# Sheet1.net
KiCad netlist of a schematic drawn in Altium Designer
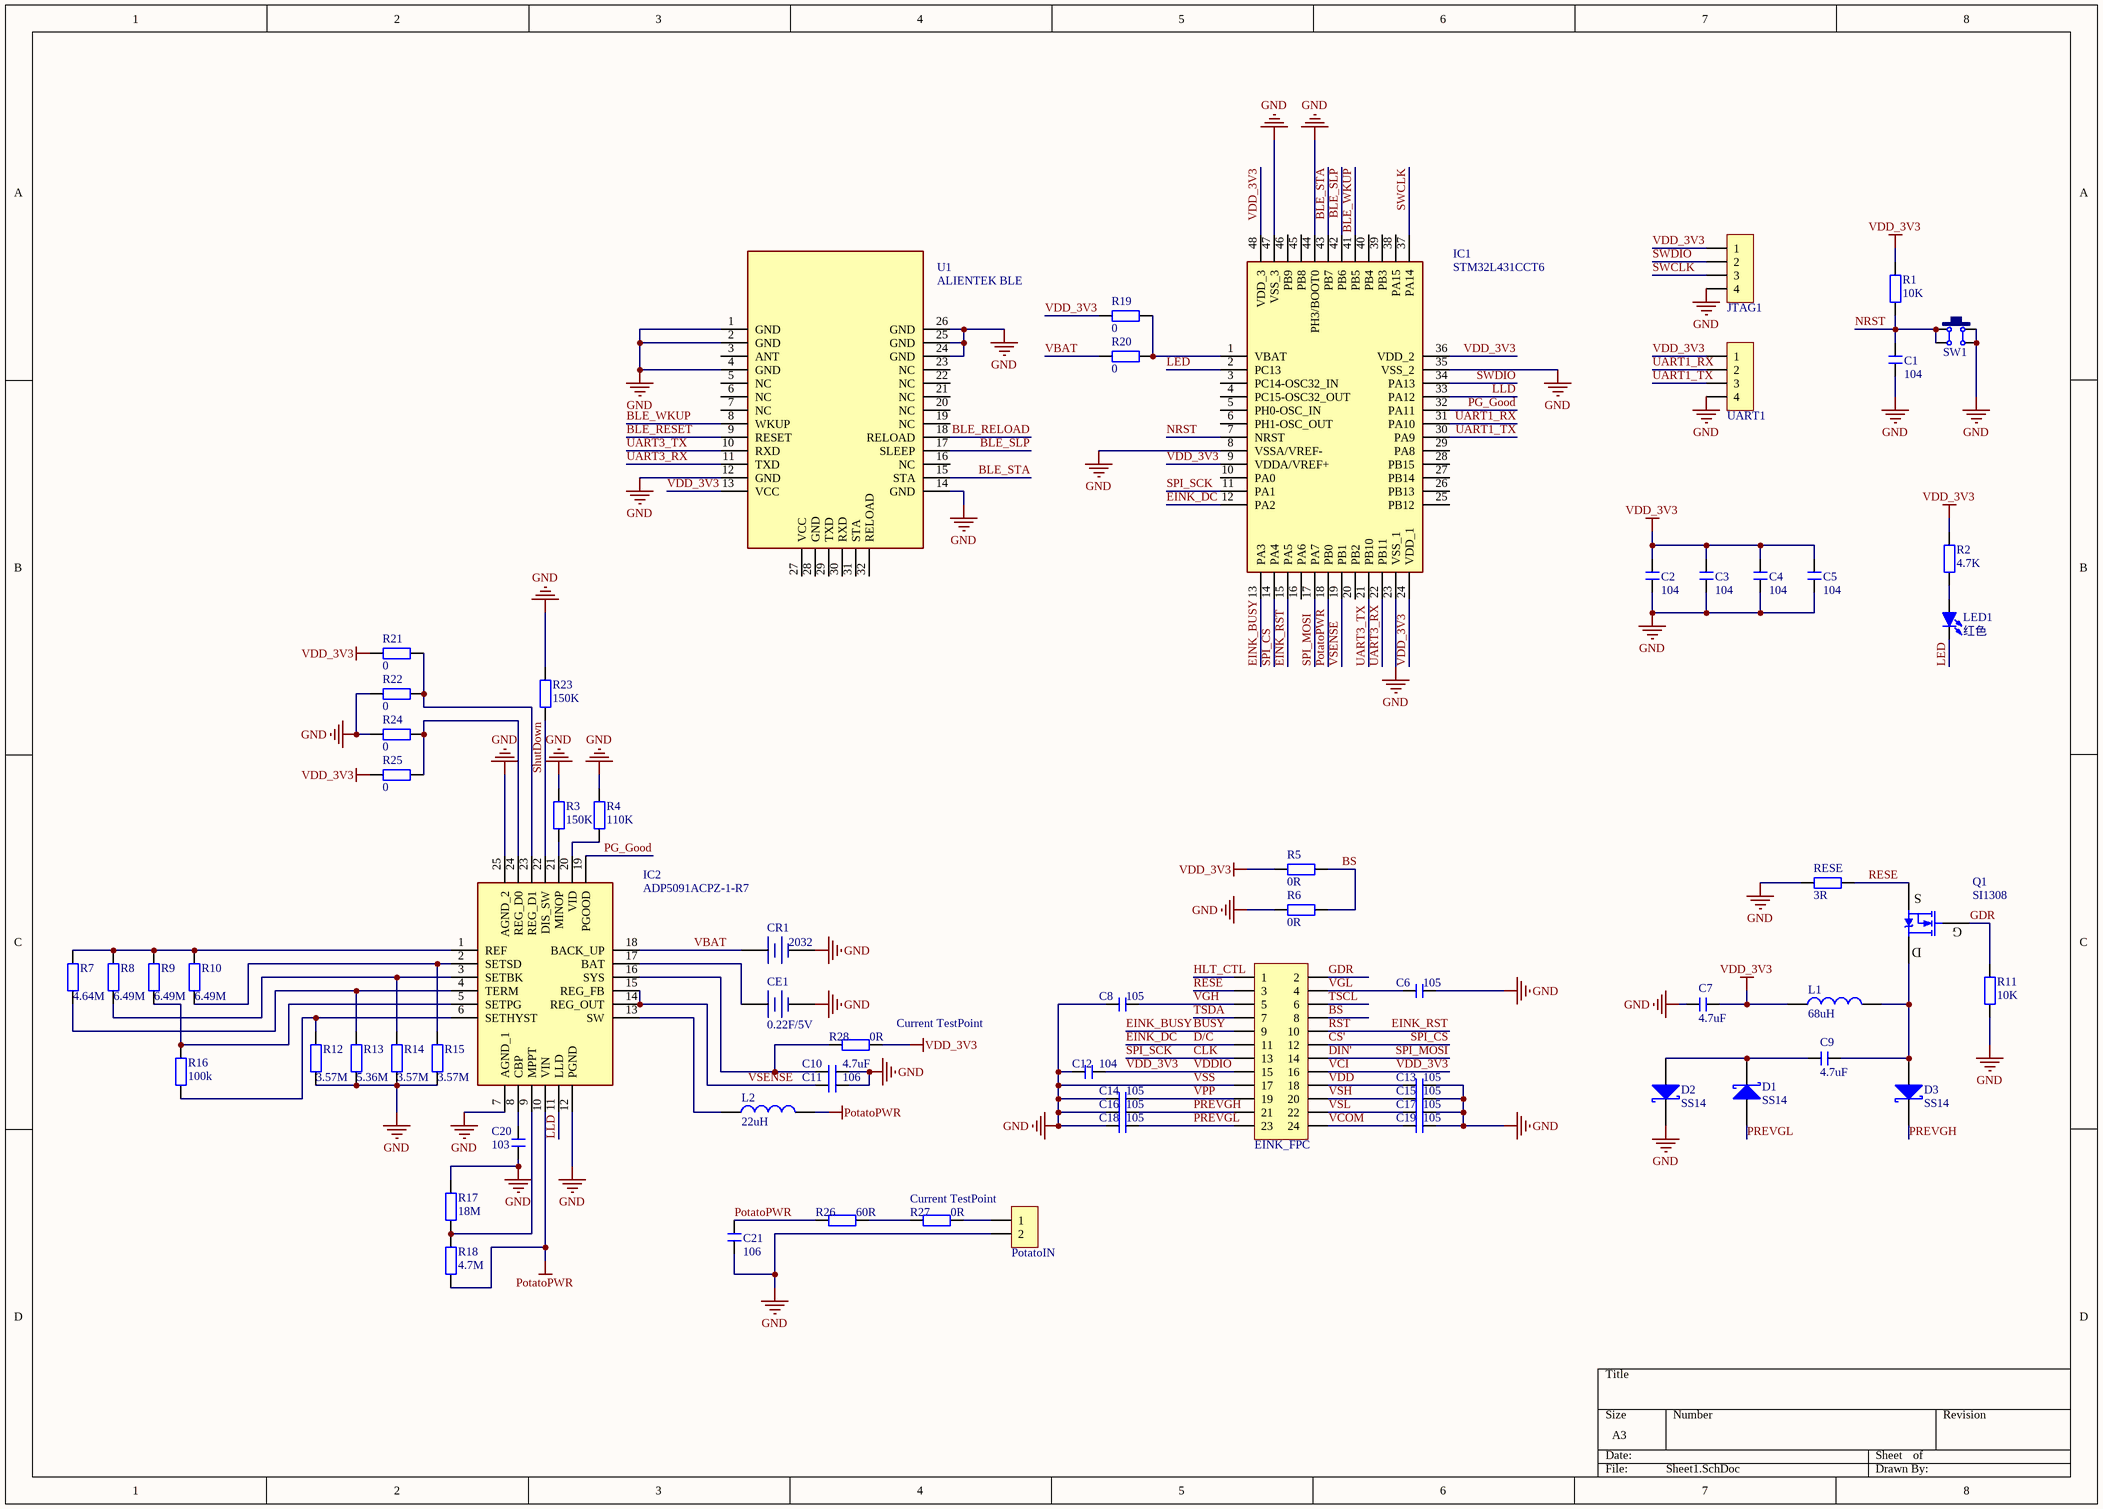
[diagram p0: Sheet1.SchDoc]

(export (version "E")
  (design (tool "Eeschema 10.0.6"))
  (components
    (comp (ref "C1")
      (value "104")
      (footprint "C 0603_L")
      (description "贴片电容")
      (libsource (lib "0.1 - 电阻-电容-电感") (part "C"))
    )
    (comp (ref "C2")
      (value "104")
      (footprint "C 0603_L")
      (description "贴片电容")
      (libsource (lib "0.1 - 电阻-电容-电感") (part "C"))
    )
    (comp (ref "C3")
      (value "104")
      (footprint "C 0603_L")
      (description "贴片电容")
      (libsource (lib "0.1 - 电阻-电容-电感") (part "C"))
    )
    (comp (ref "C4")
      (value "104")
      (footprint "C 0603_L")
      (description "贴片电容")
      (libsource (lib "0.1 - 电阻-电容-电感") (part "C"))
    )
    (comp (ref "C5")
      (value "104")
      (footprint "C 0603_L")
      (description "贴片电容")
      (libsource (lib "0.1 - 电阻-电容-电感") (part "C"))
    )
    (comp (ref "C6")
      (value "105")
      (footprint "C 0603_L")
      (description "贴片电容")
      (libsource (lib "0.1 - 电阻-电容-电感") (part "C"))
    )
    (comp (ref "C7")
      (value "4.7uF")
      (footprint "C 0603_L")
      (description "贴片电容")
      (libsource (lib "0.1 - 电阻-电容-电感") (part "C"))
    )
    (comp (ref "C8")
      (value "105")
      (footprint "C 0603_L")
      (description "贴片电容")
      (libsource (lib "0.1 - 电阻-电容-电感") (part "C"))
    )
    (comp (ref "C9")
      (value "4.7uF")
      (footprint "C 0603_L")
      (description "贴片电容")
      (libsource (lib "0.1 - 电阻-电容-电感") (part "C"))
    )
    (comp (ref "C10")
      (value "4.7uF")
      (footprint "C 0603_L")
      (description "贴片电容")
      (libsource (lib "0.1 - 电阻-电容-电感") (part "C"))
    )
    (comp (ref "C11")
      (value "106")
      (footprint "C 0603_L")
      (description "贴片电容")
      (libsource (lib "0.1 - 电阻-电容-电感") (part "C"))
    )
    (comp (ref "C12")
      (value "104")
      (footprint "C 0603_L")
      (description "贴片电容")
      (libsource (lib "0.1 - 电阻-电容-电感") (part "C"))
    )
    (comp (ref "C13")
      (value "105")
      (footprint "C 0603_L")
      (description "贴片电容")
      (libsource (lib "0.1 - 电阻-电容-电感") (part "C"))
    )
    (comp (ref "C14")
      (value "105")
      (footprint "C 0603_L")
      (description "贴片电容")
      (libsource (lib "0.1 - 电阻-电容-电感") (part "C"))
    )
    (comp (ref "C15")
      (value "105")
      (footprint "C 0603_L")
      (description "贴片电容")
      (libsource (lib "0.1 - 电阻-电容-电感") (part "C"))
    )
    (comp (ref "C16")
      (value "105")
      (footprint "C 0603_L")
      (description "贴片电容")
      (libsource (lib "0.1 - 电阻-电容-电感") (part "C"))
    )
    (comp (ref "C17")
      (value "105")
      (footprint "C 0603_L")
      (description "贴片电容")
      (libsource (lib "0.1 - 电阻-电容-电感") (part "C"))
    )
    (comp (ref "C18")
      (value "105")
      (footprint "C 0603_L")
      (description "贴片电容")
      (libsource (lib "0.1 - 电阻-电容-电感") (part "C"))
    )
    (comp (ref "C19")
      (value "105")
      (footprint "C 0603_L")
      (description "贴片电容")
      (libsource (lib "0.1 - 电阻-电容-电感") (part "C"))
    )
    (comp (ref "C20")
      (value "103")
      (footprint "C 0603_L")
      (description "贴片电容")
      (libsource (lib "0.1 - 电阻-电容-电感") (part "C"))
    )
    (comp (ref "C21")
      (value "106")
      (footprint "C 0603_L")
      (description "贴片电容")
      (libsource (lib "0.1 - 电阻-电容-电感") (part "C"))
    )
    (comp (ref "CE1")
      (value "0.22F/5V")
      (footprint "CAP 5.0*12.5*20 - BK")
      (description "微型电池")
      (fields (field (name "版权归属") "封装库来自淘宝 ID：黄晶宝石"))
      (libsource (lib "4.1 - 未分类器件") (part "CR-3V"))
    )
    (comp (ref "CR1")
      (value "2032")
      (footprint "CR2032_A")
      (description "微型电池")
      (fields (field (name "版权归属") "封装库来自淘宝 ID：黄晶宝石"))
      (libsource (lib "4.1 - 未分类器件") (part "CR-3V"))
    )
    (comp (ref "D1")
      (value "SS14")
      (footprint "SOD-123")
      (description "肖特基二极管")
      (libsource (lib "0.2 -  二极管-整流桥") (part "SS14"))
    )
    (comp (ref "D2")
      (value "SS14")
      (footprint "SOD-123")
      (description "肖特基二极管")
      (libsource (lib "0.2 -  二极管-整流桥") (part "SS14"))
    )
    (comp (ref "D3")
      (value "SS14")
      (footprint "SOD-123")
      (description "肖特基二极管")
      (libsource (lib "0.2 -  二极管-整流桥") (part "SS14"))
    )
    (comp (ref "EINK_FPC")
      (value "Header 2X11")
      (footprint "FPC0.5 2H-WS-24P")
      (description "12*2P接插件")
      (fields (field (name "版权归属") "封装库来自淘宝卖家 ID：黄晶宝石"))
      (libsource (lib "5.3 - 接插件-脚距2.54 (100mil) ") (part "Header 12X2"))
    )
    (comp (ref "IC1")
      (value "STM32L431CCT6")
      (footprint "SkylakeADPcbLib:QFP50P900X900X160-48N")
      (description "Integrated Circuit")
      (libsource (lib "*") (part "STM32L431CCT6"))
    )
    (comp (ref "IC2")
      (value "ADP5091ACPZ-1-R7")
      (footprint "SkylakeADPcbLib:QFN50P400X400X80-25N-D")
      (description "Integrated Circuit")
      (libsource (lib "*") (part "ADP5091ACPZ-1-R7"))
    )
    (comp (ref "JTAG1")
      (value "HDR-1X4")
      (footprint "XH2.54-LI-4P")
      (description "4P接插件")
      (libsource (lib "5.0 - 接插件-脚距1.25") (part "Header 4"))
    )
    (comp (ref "L1")
      (value "68uH")
      (footprint "CDRH74")
      (description "小功率贴片电感")
      (libsource (lib "0.1 - 电阻-电容-电感") (part "L"))
    )
    (comp (ref "L2")
      (value "22uH")
      (footprint "CDRH74")
      (description "小功率贴片电感")
      (libsource (lib "0.1 - 电阻-电容-电感") (part "L"))
    )
    (comp (ref "LED1")
      (value "红色")
      (footprint "LED 0603R")
      (description "贴片LED")
      (fields (field (name "版权归属") "封装库来自淘宝 ID：黄晶宝石"))
      (libsource (lib "0.3 - LED发光二极管") (part "LED-SMD"))
    )
    (comp (ref "PotatoIN")
      (value "HDR-1X2")
      (footprint "XH2.54-LI-2P")
      (description "2P接插件")
      (fields (field (name "版权归属") "封装库来自淘宝 ID：黄晶宝石"))
      (libsource (lib "5.3 - 接插件-脚距2.54 (100mil) ") (part "Header 2"))
    )
    (comp (ref "Q1")
      (value "SI1308")
      (footprint "SOT23-3N")
      (description "N沟道场效应管")
      (libsource (lib "0.5 - 场效应管-可控硅") (part "SI2302"))
    )
    (comp (ref "R1")
      (value "10K")
      (footprint "R 0603_L")
      (description "贴片电阻")
      (fields (field (name "版权归属") "来自淘宝 ID：黄晶宝石"))
      (libsource (lib "0.1 - 电阻-电容-电感") (part "R"))
    )
    (comp (ref "R2")
      (value "4.7K")
      (footprint "R 0603_L")
      (description "贴片电阻")
      (fields (field (name "版权归属") "来自淘宝 ID：黄晶宝石"))
      (libsource (lib "0.1 - 电阻-电容-电感") (part "R"))
    )
    (comp (ref "R3")
      (value "150K")
      (footprint "R 0603_L")
      (description "贴片电阻")
      (fields (field (name "版权归属") "来自淘宝 ID：黄晶宝石"))
      (libsource (lib "0.1 - 电阻-电容-电感") (part "R"))
    )
    (comp (ref "R4")
      (value "110K")
      (footprint "R 0603_L")
      (description "贴片电阻")
      (fields (field (name "版权归属") "来自淘宝 ID：黄晶宝石"))
      (libsource (lib "0.1 - 电阻-电容-电感") (part "R"))
    )
    (comp (ref "R5")
      (value "0R")
      (footprint "R 0603_L")
      (description "贴片电阻")
      (fields (field (name "版权归属") "来自淘宝 ID：黄晶宝石"))
      (libsource (lib "0.1 - 电阻-电容-电感") (part "R"))
    )
    (comp (ref "R6")
      (value "0R")
      (footprint "R 0603_L")
      (description "贴片电阻")
      (fields (field (name "版权归属") "来自淘宝 ID：黄晶宝石"))
      (libsource (lib "0.1 - 电阻-电容-电感") (part "R"))
    )
    (comp (ref "R7")
      (value "4.64M")
      (footprint "R 0603_L")
      (description "贴片电阻")
      (fields (field (name "版权归属") "来自淘宝 ID：黄晶宝石"))
      (libsource (lib "0.1 - 电阻-电容-电感") (part "R"))
    )
    (comp (ref "R8")
      (value "6.49M")
      (footprint "R 0603_L")
      (description "贴片电阻")
      (fields (field (name "版权归属") "来自淘宝 ID：黄晶宝石"))
      (libsource (lib "0.1 - 电阻-电容-电感") (part "R"))
    )
    (comp (ref "R9")
      (value "6.49M")
      (footprint "R 0603_L")
      (description "贴片电阻")
      (fields (field (name "版权归属") "来自淘宝 ID：黄晶宝石"))
      (libsource (lib "0.1 - 电阻-电容-电感") (part "R"))
    )
    (comp (ref "R10")
      (value "6.49M")
      (footprint "R 0603_L")
      (description "贴片电阻")
      (fields (field (name "版权归属") "来自淘宝 ID：黄晶宝石"))
      (libsource (lib "0.1 - 电阻-电容-电感") (part "R"))
    )
    (comp (ref "R11")
      (value "10K")
      (footprint "R 0603_L")
      (description "贴片电阻")
      (fields (field (name "版权归属") "来自淘宝 ID：黄晶宝石"))
      (libsource (lib "0.1 - 电阻-电容-电感") (part "R"))
    )
    (comp (ref "R12")
      (value "3.57M")
      (footprint "R 0603_L")
      (description "贴片电阻")
      (fields (field (name "版权归属") "来自淘宝 ID：黄晶宝石"))
      (libsource (lib "0.1 - 电阻-电容-电感") (part "R"))
    )
    (comp (ref "R13")
      (value "5.36M")
      (footprint "R 0603_L")
      (description "贴片电阻")
      (fields (field (name "版权归属") "来自淘宝 ID：黄晶宝石"))
      (libsource (lib "0.1 - 电阻-电容-电感") (part "R"))
    )
    (comp (ref "R14")
      (value "3.57M")
      (footprint "R 0603_L")
      (description "贴片电阻")
      (fields (field (name "版权归属") "来自淘宝 ID：黄晶宝石"))
      (libsource (lib "0.1 - 电阻-电容-电感") (part "R"))
    )
    (comp (ref "R15")
      (value "3.57M")
      (footprint "R 0603_L")
      (description "贴片电阻")
      (fields (field (name "版权归属") "来自淘宝 ID：黄晶宝石"))
      (libsource (lib "0.1 - 电阻-电容-电感") (part "R"))
    )
    (comp (ref "R16")
      (value "100k")
      (footprint "R 0603_L")
      (description "贴片电阻")
      (fields (field (name "版权归属") "来自淘宝 ID：黄晶宝石"))
      (libsource (lib "0.1 - 电阻-电容-电感") (part "R"))
    )
    (comp (ref "R17")
      (value "18M")
      (footprint "R 0603_L")
      (description "贴片电阻")
      (fields (field (name "版权归属") "来自淘宝 ID：黄晶宝石"))
      (libsource (lib "0.1 - 电阻-电容-电感") (part "R"))
    )
    (comp (ref "R18")
      (value "4.7M")
      (footprint "R 0603_L")
      (description "贴片电阻")
      (fields (field (name "版权归属") "来自淘宝 ID：黄晶宝石"))
      (libsource (lib "0.1 - 电阻-电容-电感") (part "R"))
    )
    (comp (ref "R19")
      (value "0")
      (footprint "R 0603_L")
      (description "贴片电阻")
      (fields (field (name "版权归属") "来自淘宝 ID：黄晶宝石"))
      (libsource (lib "0.1 - 电阻-电容-电感") (part "R"))
    )
    (comp (ref "R20")
      (value "0")
      (footprint "R 0603_L")
      (description "贴片电阻")
      (fields (field (name "版权归属") "来自淘宝 ID：黄晶宝石"))
      (libsource (lib "0.1 - 电阻-电容-电感") (part "R"))
    )
    (comp (ref "R21")
      (value "0")
      (footprint "R 0603_L")
      (description "贴片电阻")
      (fields (field (name "版权归属") "来自淘宝 ID：黄晶宝石"))
      (libsource (lib "0.1 - 电阻-电容-电感") (part "R"))
    )
    (comp (ref "R22")
      (value "0")
      (footprint "R 0603_L")
      (description "贴片电阻")
      (fields (field (name "版权归属") "来自淘宝 ID：黄晶宝石"))
      (libsource (lib "0.1 - 电阻-电容-电感") (part "R"))
    )
    (comp (ref "R23")
      (value "150K")
      (footprint "R 0603_L")
      (description "贴片电阻")
      (fields (field (name "版权归属") "来自淘宝 ID：黄晶宝石"))
      (libsource (lib "0.1 - 电阻-电容-电感") (part "R"))
    )
    (comp (ref "R24")
      (value "0")
      (footprint "R 0603_L")
      (description "贴片电阻")
      (fields (field (name "版权归属") "来自淘宝 ID：黄晶宝石"))
      (libsource (lib "0.1 - 电阻-电容-电感") (part "R"))
    )
    (comp (ref "R25")
      (value "0")
      (footprint "R 0603_L")
      (description "贴片电阻")
      (fields (field (name "版权归属") "来自淘宝 ID：黄晶宝石"))
      (libsource (lib "0.1 - 电阻-电容-电感") (part "R"))
    )
    (comp (ref "R26")
      (value "60R")
      (footprint "R 0805_L")
      (description "贴片电阻")
      (fields (field (name "版权归属") "来自淘宝 ID：黄晶宝石"))
      (libsource (lib "0.1 - 电阻-电容-电感") (part "R"))
    )
    (comp (ref "R27")
      (value "0R")
      (footprint "R 1210_L")
      (description "贴片电阻")
      (fields (field (name "版权归属") "来自淘宝 ID：黄晶宝石"))
      (libsource (lib "0.1 - 电阻-电容-电感") (part "R"))
    )
    (comp (ref "R28")
      (value "0R")
      (footprint "R 1210_L")
      (description "贴片电阻")
      (fields (field (name "版权归属") "来自淘宝 ID：黄晶宝石"))
      (libsource (lib "0.1 - 电阻-电容-电感") (part "R"))
    )
    (comp (ref "RESE")
      (value "3R")
      (footprint "R 0603_L")
      (description "贴片电阻")
      (fields (field (name "版权归属") "来自淘宝 ID：黄晶宝石"))
      (libsource (lib "0.1 - 电阻-电容-电感") (part "R"))
    )
    (comp (ref "SW1")
      (value "6x6x5")
      (footprint "TSW SMD-6*6*4.3")
      (description "贴片6x6轻触开关")
      (fields (field (name "版权归属") "封装库来自淘宝 ID：黄晶宝石"))
      (libsource (lib "0.7 - 常用按键-开关") (part "TSW SMD-6x6"))
    )
    (comp (ref "U1")
      (value "ALIENTEK BLE")
      (footprint "ALIENTEK BLE")
      (libsource (lib "SkylakeADSchLib") (part "ALIENTEK BLE"))
    )
    (comp (ref "UART1")
      (value "HDR-1X4")
      (footprint "XH2.54-LI-4P")
      (description "4P接插件")
      (libsource (lib "5.0 - 接插件-脚距1.25") (part "Header 4"))
    )
  )
  (nets
    (net (code "1") (name "/BLE_RELOAD") (class "Default")
      (node (ref "U1") (pin "18") (pinfunction "RELOAD_18") (pintype "passive"))
    )
    (net (code "2") (name "/BLE_RESET") (class "Default")
      (node (ref "U1") (pin "9") (pinfunction "RESET_9") (pintype "passive"))
    )
    (net (code "3") (name "/BLE_SLP") (class "Default")
      (node (ref "IC1") (pin "42") (pinfunction "PB6_42") (pintype "passive"))
      (node (ref "U1") (pin "17") (pinfunction "SLEEP_17") (pintype "passive"))
    )
    (net (code "4") (name "/BLE_STA") (class "Default")
      (node (ref "IC1") (pin "43") (pinfunction "PB7_43") (pintype "passive"))
      (node (ref "U1") (pin "15") (pinfunction "STA_15") (pintype "passive"))
    )
    (net (code "5") (name "/BLE_WKUP") (class "Default")
      (node (ref "IC1") (pin "41") (pinfunction "PB5_41") (pintype "passive"))
      (node (ref "U1") (pin "8") (pinfunction "WKUP_8") (pintype "passive"))
    )
    (net (code "6") (name "/BS") (class "Default")
      (node (ref "EINK_FPC") (pin "8") (pinfunction "8_8") (pintype "passive"))
      (node (ref "R5") (pin "2") (pinfunction "2_2") (pintype "passive"))
      (node (ref "R6") (pin "2") (pinfunction "2_2") (pintype "passive"))
    )
    (net (code "7") (name "/BUSY") (class "Default")
      (node (ref "EINK_FPC") (pin "9") (pinfunction "9_9") (pintype "passive"))
      (node (ref "IC1") (pin "13") (pinfunction "PA3_13") (pintype "passive"))
    )
    (net (code "8") (name "/CLK") (class "Default")
      (node (ref "EINK_FPC") (pin "13") (pinfunction "13_13") (pintype "passive"))
      (node (ref "IC1") (pin "11") (pinfunction "PA1_11") (pintype "passive"))
    )
    (net (code "9") (name "/CS'") (class "Default")
      (node (ref "EINK_FPC") (pin "12") (pinfunction "12_12") (pintype "passive"))
      (node (ref "IC1") (pin "14") (pinfunction "PA4_14") (pintype "passive"))
    )
    (net (code "10") (name "/DIN'") (class "Default")
      (node (ref "EINK_FPC") (pin "14") (pinfunction "14_14") (pintype "passive"))
      (node (ref "IC1") (pin "17") (pinfunction "PA7_17") (pintype "passive"))
    )
    (net (code "11") (name "/D{slash}C") (class "Default")
      (node (ref "EINK_FPC") (pin "11") (pinfunction "11_11") (pintype "passive"))
      (node (ref "IC1") (pin "12") (pinfunction "PA2_12") (pintype "passive"))
    )
    (net (code "12") (name "/EINK_RST") (class "Default")
      (node (ref "EINK_FPC") (pin "10") (pinfunction "10_10") (pintype "passive"))
      (node (ref "IC1") (pin "15") (pinfunction "PA5_15") (pintype "passive"))
    )
    (net (code "13") (name "/GDR") (class "Default")
      (node (ref "EINK_FPC") (pin "2") (pinfunction "2_2") (pintype "passive"))
      (node (ref "Q1") (pin "1") (pinfunction "G_1") (pintype "passive"))
      (node (ref "R11") (pin "2") (pinfunction "2_2") (pintype "passive"))
    )
    (net (code "14") (name "/HLT_CTL") (class "Default")
      (node (ref "EINK_FPC") (pin "1") (pinfunction "1_1") (pintype "passive"))
    )
    (net (code "15") (name "/LED") (class "Default")
      (node (ref "IC1") (pin "2") (pinfunction "PC13_2") (pintype "passive"))
      (node (ref "LED1") (pin "2") (pinfunction "K_2") (pintype "passive"))
    )
    (net (code "16") (name "/LLD") (class "Default")
      (node (ref "IC1") (pin "33") (pinfunction "PA12_33") (pintype "passive"))
      (node (ref "IC2") (pin "11") (pinfunction "LLD_11") (pintype "passive"))
    )
    (net (code "17") (name "/NRST") (class "Default")
      (node (ref "C1") (pin "2") (pinfunction "2_2") (pintype "passive"))
      (node (ref "IC1") (pin "7") (pinfunction "NRST_7") (pintype "passive"))
      (node (ref "R1") (pin "1") (pinfunction "1_1") (pintype "passive"))
      (node (ref "SW1") (pin "1") (pinfunction "1_1") (pintype "passive"))
      (node (ref "SW1") (pin "4") (pinfunction "4_4") (pintype "passive"))
    )
    (net (code "18") (name "/PG_Good") (class "Default")
      (node (ref "IC1") (pin "32") (pinfunction "PA11_32") (pintype "passive"))
      (node (ref "IC2") (pin "19") (pinfunction "PGOOD_19") (pintype "passive"))
    )
    (net (code "19") (name "/PREVGH") (class "Default")
      (node (ref "C16") (pin "2") (pinfunction "2_2") (pintype "passive"))
      (node (ref "D3") (pin "2") (pinfunction "K_2") (pintype "passive"))
      (node (ref "EINK_FPC") (pin "21") (pinfunction "21_21") (pintype "passive"))
    )
    (net (code "20") (name "/PREVGL") (class "Default")
      (node (ref "C18") (pin "2") (pinfunction "2_2") (pintype "passive"))
      (node (ref "D1") (pin "1") (pinfunction "A_1") (pintype "passive"))
      (node (ref "EINK_FPC") (pin "23") (pinfunction "23_23") (pintype "passive"))
    )
    (net (code "21") (name "/RESE") (class "Default")
      (node (ref "EINK_FPC") (pin "3") (pinfunction "3_3") (pintype "passive"))
      (node (ref "Q1") (pin "2") (pinfunction "S_2") (pintype "passive"))
      (node (ref "RESE") (pin "1") (pinfunction "1_1") (pintype "passive"))
    )
    (net (code "22") (name "/SWCLK") (class "Default")
      (node (ref "IC1") (pin "37") (pinfunction "PA14_37") (pintype "passive"))
      (node (ref "JTAG1") (pin "3") (pinfunction "3_3") (pintype "passive"))
    )
    (net (code "23") (name "/SWDIO") (class "Default")
      (node (ref "IC1") (pin "34") (pinfunction "PA13_34") (pintype "passive"))
      (node (ref "JTAG1") (pin "2") (pinfunction "2_2") (pintype "passive"))
    )
    (net (code "24") (name "/ShutDown") (class "Default")
      (node (ref "IC2") (pin "22") (pinfunction "DIS_SW_22") (pintype "passive"))
      (node (ref "R23") (pin "1") (pinfunction "1_1") (pintype "passive"))
    )
    (net (code "25") (name "/TSCL") (class "Default")
      (node (ref "EINK_FPC") (pin "6") (pinfunction "6_6") (pintype "passive"))
    )
    (net (code "26") (name "/TSDA") (class "Default")
      (node (ref "EINK_FPC") (pin "7") (pinfunction "7_7") (pintype "passive"))
    )
    (net (code "27") (name "/UART1_RX") (class "Default")
      (node (ref "IC1") (pin "31") (pinfunction "PA10_31") (pintype "passive"))
      (node (ref "UART1") (pin "2") (pinfunction "2_2") (pintype "passive"))
    )
    (net (code "28") (name "/UART1_TX") (class "Default")
      (node (ref "IC1") (pin "30") (pinfunction "PA9_30") (pintype "passive"))
      (node (ref "UART1") (pin "3") (pinfunction "3_3") (pintype "passive"))
    )
    (net (code "29") (name "/UART3_RX") (class "Default")
      (node (ref "IC1") (pin "22") (pinfunction "PB11_22") (pintype "passive"))
      (node (ref "U1") (pin "11") (pinfunction "TXD_11") (pintype "passive"))
    )
    (net (code "30") (name "/UART3_TX") (class "Default")
      (node (ref "IC1") (pin "21") (pinfunction "PB10_21") (pintype "passive"))
      (node (ref "U1") (pin "10") (pinfunction "RXD_10") (pintype "passive"))
    )
    (net (code "31") (name "/VBAT") (class "Default")
      (node (ref "CR1") (pin "1") (pinfunction "DC+_1") (pintype "passive"))
      (node (ref "IC2") (pin "18") (pinfunction "BACK_UP_18") (pintype "passive"))
      (node (ref "R20") (pin "2") (pinfunction "2_2") (pintype "passive"))
    )
    (net (code "32") (name "/VCOM") (class "Default")
      (node (ref "C19") (pin "1") (pinfunction "1_1") (pintype "passive"))
      (node (ref "EINK_FPC") (pin "24") (pinfunction "24_24") (pintype "passive"))
    )
    (net (code "33") (name "/VDD") (class "Default")
      (node (ref "C13") (pin "1") (pinfunction "1_1") (pintype "passive"))
      (node (ref "EINK_FPC") (pin "18") (pinfunction "18_18") (pintype "passive"))
    )
    (net (code "34") (name "/VGH") (class "Default")
      (node (ref "C8") (pin "2") (pinfunction "2_2") (pintype "passive"))
      (node (ref "EINK_FPC") (pin "5") (pinfunction "5_5") (pintype "passive"))
    )
    (net (code "35") (name "/VGL") (class "Default")
      (node (ref "C6") (pin "1") (pinfunction "1_1") (pintype "passive"))
      (node (ref "EINK_FPC") (pin "4") (pinfunction "4_4") (pintype "passive"))
    )
    (net (code "36") (name "/VPP") (class "Default")
      (node (ref "C14") (pin "2") (pinfunction "2_2") (pintype "passive"))
      (node (ref "EINK_FPC") (pin "19") (pinfunction "19_19") (pintype "passive"))
    )
    (net (code "37") (name "/VSENSE") (class "Default")
      (node (ref "C11") (pin "2") (pinfunction "2_2") (pintype "passive"))
      (node (ref "IC1") (pin "19") (pinfunction "PB1_19") (pintype "passive"))
      (node (ref "IC2") (pin "14") (pinfunction "REG_OUT_14") (pintype "passive"))
      (node (ref "IC2") (pin "15") (pinfunction "REG_FB_15") (pintype "passive"))
    )
    (net (code "38") (name "/VSH") (class "Default")
      (node (ref "C15") (pin "1") (pinfunction "1_1") (pintype "passive"))
      (node (ref "EINK_FPC") (pin "20") (pinfunction "20_20") (pintype "passive"))
    )
    (net (code "39") (name "/VSL") (class "Default")
      (node (ref "C17") (pin "1") (pinfunction "1_1") (pintype "passive"))
      (node (ref "EINK_FPC") (pin "22") (pinfunction "22_22") (pintype "passive"))
    )
    (net (code "40") (name "GND") (class "Default")
      (node (ref "C1") (pin "1") (pinfunction "1_1") (pintype "passive"))
      (node (ref "C10") (pin "1") (pinfunction "1_1") (pintype "passive"))
      (node (ref "C11") (pin "1") (pinfunction "1_1") (pintype "passive"))
      (node (ref "C12") (pin "2") (pinfunction "2_2") (pintype "passive"))
      (node (ref "C13") (pin "2") (pinfunction "2_2") (pintype "passive"))
      (node (ref "C14") (pin "1") (pinfunction "1_1") (pintype "passive"))
      (node (ref "C15") (pin "2") (pinfunction "2_2") (pintype "passive"))
      (node (ref "C16") (pin "1") (pinfunction "1_1") (pintype "passive"))
      (node (ref "C17") (pin "2") (pinfunction "2_2") (pintype "passive"))
      (node (ref "C18") (pin "1") (pinfunction "1_1") (pintype "passive"))
      (node (ref "C19") (pin "2") (pinfunction "2_2") (pintype "passive"))
      (node (ref "C2") (pin "1") (pinfunction "1_1") (pintype "passive"))
      (node (ref "C20") (pin "1") (pinfunction "1_1") (pintype "passive"))
      (node (ref "C21") (pin "1") (pinfunction "1_1") (pintype "passive"))
      (node (ref "C3") (pin "1") (pinfunction "1_1") (pintype "passive"))
      (node (ref "C4") (pin "1") (pinfunction "1_1") (pintype "passive"))
      (node (ref "C5") (pin "1") (pinfunction "1_1") (pintype "passive"))
      (node (ref "C6") (pin "2") (pinfunction "2_2") (pintype "passive"))
      (node (ref "C7") (pin "1") (pinfunction "1_1") (pintype "passive"))
      (node (ref "C8") (pin "1") (pinfunction "1_1") (pintype "passive"))
      (node (ref "CE1") (pin "2") (pinfunction "DC-_2") (pintype "passive"))
      (node (ref "CR1") (pin "2") (pinfunction "DC-_2") (pintype "passive"))
      (node (ref "D2") (pin "2") (pinfunction "K_2") (pintype "passive"))
      (node (ref "EINK_FPC") (pin "17") (pinfunction "17_17") (pintype "passive"))
      (node (ref "IC1") (pin "23") (pinfunction "VSS_1_23") (pintype "passive"))
      (node (ref "IC1") (pin "35") (pinfunction "VSS_2_35") (pintype "passive"))
      (node (ref "IC1") (pin "44") (pinfunction "PH3/BOOT0_44") (pintype "passive"))
      (node (ref "IC1") (pin "47") (pinfunction "VSS_3_47") (pintype "passive"))
      (node (ref "IC1") (pin "8") (pinfunction "VSSA/VREF-_8") (pintype "passive"))
      (node (ref "IC2") (pin "12") (pinfunction "PGND_12") (pintype "passive"))
      (node (ref "IC2") (pin "25") (pinfunction "AGND_2_25") (pintype "passive"))
      (node (ref "IC2") (pin "7") (pinfunction "AGND_1_7") (pintype "passive"))
      (node (ref "JTAG1") (pin "4") (pinfunction "4_4") (pintype "passive"))
      (node (ref "PotatoIN") (pin "2") (pinfunction "2_2") (pintype "passive"))
      (node (ref "R11") (pin "1") (pinfunction "1_1") (pintype "passive"))
      (node (ref "R12") (pin "1") (pinfunction "1_1") (pintype "passive"))
      (node (ref "R13") (pin "1") (pinfunction "1_1") (pintype "passive"))
      (node (ref "R14") (pin "1") (pinfunction "1_1") (pintype "passive"))
      (node (ref "R15") (pin "1") (pinfunction "1_1") (pintype "passive"))
      (node (ref "R17") (pin "2") (pinfunction "2_2") (pintype "passive"))
      (node (ref "R22") (pin "2") (pinfunction "2_2") (pintype "passive"))
      (node (ref "R23") (pin "2") (pinfunction "2_2") (pintype "passive"))
      (node (ref "R24") (pin "2") (pinfunction "2_2") (pintype "passive"))
      (node (ref "R3") (pin "2") (pinfunction "2_2") (pintype "passive"))
      (node (ref "R4") (pin "2") (pinfunction "2_2") (pintype "passive"))
      (node (ref "R6") (pin "1") (pinfunction "1_1") (pintype "passive"))
      (node (ref "RESE") (pin "2") (pinfunction "2_2") (pintype "passive"))
      (node (ref "SW1") (pin "2") (pinfunction "2_2") (pintype "passive"))
      (node (ref "SW1") (pin "3") (pinfunction "3_3") (pintype "passive"))
      (node (ref "U1") (pin "1") (pinfunction "GND_1") (pintype "passive"))
      (node (ref "U1") (pin "12") (pinfunction "GND_12") (pintype "passive"))
      (node (ref "U1") (pin "14") (pinfunction "GND_14") (pintype "passive"))
      (node (ref "U1") (pin "2") (pinfunction "GND_2") (pintype "passive"))
      (node (ref "U1") (pin "24") (pinfunction "GND_24") (pintype "passive"))
      (node (ref "U1") (pin "25") (pinfunction "GND_25") (pintype "passive"))
      (node (ref "U1") (pin "26") (pinfunction "GND_26") (pintype "passive"))
      (node (ref "U1") (pin "4") (pinfunction "GND_4") (pintype "passive"))
      (node (ref "UART1") (pin "4") (pinfunction "4_4") (pintype "passive"))
    )
    (net (code "41") (name "Net-(CE1-DC+)") (class "Default")
      (node (ref "CE1") (pin "1") (pinfunction "DC+_1") (pintype "passive"))
      (node (ref "IC2") (pin "17") (pinfunction "BAT_17") (pintype "passive"))
    )
    (net (code "42") (name "Net-(D1-K)") (class "Default")
      (node (ref "C9") (pin "1") (pinfunction "1_1") (pintype "passive"))
      (node (ref "D1") (pin "2") (pinfunction "K_2") (pintype "passive"))
      (node (ref "D2") (pin "1") (pinfunction "A_1") (pintype "passive"))
    )
    (net (code "43") (name "Net-(D3-A)") (class "Default")
      (node (ref "C9") (pin "2") (pinfunction "2_2") (pintype "passive"))
      (node (ref "D3") (pin "1") (pinfunction "A_1") (pintype "passive"))
      (node (ref "L1") (pin "2") (pinfunction "2_2") (pintype "passive"))
      (node (ref "Q1") (pin "3") (pinfunction "D_3") (pintype "passive"))
    )
    (net (code "44") (name "Net-(IC1-VBAT)") (class "Default")
      (node (ref "IC1") (pin "1") (pinfunction "VBAT_1") (pintype "passive"))
      (node (ref "R19") (pin "1") (pinfunction "1_1") (pintype "passive"))
      (node (ref "R20") (pin "1") (pinfunction "1_1") (pintype "passive"))
    )
    (net (code "45") (name "Net-(IC2-CBP)") (class "Default")
      (node (ref "C20") (pin "2") (pinfunction "2_2") (pintype "passive"))
      (node (ref "IC2") (pin "8") (pinfunction "CBP_8") (pintype "passive"))
    )
    (net (code "46") (name "Net-(IC2-MINOP)") (class "Default")
      (node (ref "IC2") (pin "21") (pinfunction "MINOP_21") (pintype "passive"))
      (node (ref "R3") (pin "1") (pinfunction "1_1") (pintype "passive"))
    )
    (net (code "47") (name "Net-(IC2-MPPT)") (class "Default")
      (node (ref "IC2") (pin "9") (pinfunction "MPPT_9") (pintype "passive"))
      (node (ref "R17") (pin "1") (pinfunction "1_1") (pintype "passive"))
      (node (ref "R18") (pin "2") (pinfunction "2_2") (pintype "passive"))
    )
    (net (code "48") (name "Net-(IC2-REF)") (class "Default")
      (node (ref "IC2") (pin "1") (pinfunction "REF_1") (pintype "passive"))
      (node (ref "R10") (pin "2") (pinfunction "2_2") (pintype "passive"))
      (node (ref "R7") (pin "2") (pinfunction "2_2") (pintype "passive"))
      (node (ref "R8") (pin "2") (pinfunction "2_2") (pintype "passive"))
      (node (ref "R9") (pin "2") (pinfunction "2_2") (pintype "passive"))
    )
    (net (code "49") (name "Net-(IC2-REG_D0)") (class "Default")
      (node (ref "IC2") (pin "24") (pinfunction "REG_D0_24") (pintype "passive"))
      (node (ref "R24") (pin "1") (pinfunction "1_1") (pintype "passive"))
      (node (ref "R25") (pin "1") (pinfunction "1_1") (pintype "passive"))
    )
    (net (code "50") (name "Net-(IC2-REG_D1)") (class "Default")
      (node (ref "IC2") (pin "23") (pinfunction "REG_D1_23") (pintype "passive"))
      (node (ref "R21") (pin "1") (pinfunction "1_1") (pintype "passive"))
      (node (ref "R22") (pin "1") (pinfunction "1_1") (pintype "passive"))
    )
    (net (code "51") (name "Net-(IC2-SETBK)") (class "Default")
      (node (ref "IC2") (pin "3") (pinfunction "SETBK_3") (pintype "passive"))
      (node (ref "R14") (pin "2") (pinfunction "2_2") (pintype "passive"))
      (node (ref "R8") (pin "1") (pinfunction "1_1") (pintype "passive"))
    )
    (net (code "52") (name "Net-(IC2-SETHYST)") (class "Default")
      (node (ref "IC2") (pin "6") (pinfunction "SETHYST_6") (pintype "passive"))
      (node (ref "R12") (pin "2") (pinfunction "2_2") (pintype "passive"))
      (node (ref "R16") (pin "1") (pinfunction "1_1") (pintype "passive"))
    )
    (net (code "53") (name "Net-(IC2-SETPG)") (class "Default")
      (node (ref "IC2") (pin "5") (pinfunction "SETPG_5") (pintype "passive"))
      (node (ref "R16") (pin "2") (pinfunction "2_2") (pintype "passive"))
      (node (ref "R9") (pin "1") (pinfunction "1_1") (pintype "passive"))
    )
    (net (code "54") (name "Net-(IC2-SETSD)") (class "Default")
      (node (ref "IC2") (pin "2") (pinfunction "SETSD_2") (pintype "passive"))
      (node (ref "R10") (pin "1") (pinfunction "1_1") (pintype "passive"))
      (node (ref "R15") (pin "2") (pinfunction "2_2") (pintype "passive"))
    )
    (net (code "55") (name "Net-(IC2-SW)") (class "Default")
      (node (ref "IC2") (pin "13") (pinfunction "SW_13") (pintype "passive"))
      (node (ref "L2") (pin "1") (pinfunction "1_1") (pintype "passive"))
    )
    (net (code "56") (name "Net-(IC2-SYS)") (class "Default")
      (node (ref "C10") (pin "2") (pinfunction "2_2") (pintype "passive"))
      (node (ref "IC2") (pin "16") (pinfunction "SYS_16") (pintype "passive"))
      (node (ref "R28") (pin "1") (pinfunction "1_1") (pintype "passive"))
    )
    (net (code "57") (name "Net-(IC2-TERM)") (class "Default")
      (node (ref "IC2") (pin "4") (pinfunction "TERM_4") (pintype "passive"))
      (node (ref "R13") (pin "2") (pinfunction "2_2") (pintype "passive"))
      (node (ref "R7") (pin "1") (pinfunction "1_1") (pintype "passive"))
    )
    (net (code "58") (name "Net-(IC2-VID)") (class "Default")
      (node (ref "IC2") (pin "20") (pinfunction "VID_20") (pintype "passive"))
      (node (ref "R4") (pin "1") (pinfunction "1_1") (pintype "passive"))
    )
    (net (code "59") (name "Net-(LED1-A)") (class "Default")
      (node (ref "LED1") (pin "1") (pinfunction "A_1") (pintype "passive"))
      (node (ref "R2") (pin "1") (pinfunction "1_1") (pintype "passive"))
    )
    (net (code "60") (name "Net-(PotatoIN-Pad1)") (class "Default")
      (node (ref "PotatoIN") (pin "1") (pinfunction "1_1") (pintype "passive"))
      (node (ref "R27") (pin "2") (pinfunction "2_2") (pintype "passive"))
    )
    (net (code "61") (name "Net-(R26-Pad2)") (class "Default")
      (node (ref "R26") (pin "2") (pinfunction "2_2") (pintype "passive"))
      (node (ref "R27") (pin "1") (pinfunction "1_1") (pintype "passive"))
    )
    (net (code "62") (name "PotatoPWR") (class "Default")
      (node (ref "C21") (pin "2") (pinfunction "2_2") (pintype "passive"))
      (node (ref "IC1") (pin "18") (pinfunction "PB0_18") (pintype "passive"))
      (node (ref "IC2") (pin "10") (pinfunction "VIN_10") (pintype "passive"))
      (node (ref "L2") (pin "2") (pinfunction "2_2") (pintype "passive"))
      (node (ref "R18") (pin "1") (pinfunction "1_1") (pintype "passive"))
      (node (ref "R26") (pin "1") (pinfunction "1_1") (pintype "passive"))
    )
    (net (code "63") (name "VDD_3V3") (class "Default")
      (node (ref "C12") (pin "1") (pinfunction "1_1") (pintype "passive"))
      (node (ref "C2") (pin "2") (pinfunction "2_2") (pintype "passive"))
      (node (ref "C3") (pin "2") (pinfunction "2_2") (pintype "passive"))
      (node (ref "C4") (pin "2") (pinfunction "2_2") (pintype "passive"))
      (node (ref "C5") (pin "2") (pinfunction "2_2") (pintype "passive"))
      (node (ref "C7") (pin "2") (pinfunction "2_2") (pintype "passive"))
      (node (ref "EINK_FPC") (pin "15") (pinfunction "15_15") (pintype "passive"))
      (node (ref "EINK_FPC") (pin "16") (pinfunction "16_16") (pintype "passive"))
      (node (ref "IC1") (pin "24") (pinfunction "VDD_1_24") (pintype "passive"))
      (node (ref "IC1") (pin "36") (pinfunction "VDD_2_36") (pintype "passive"))
      (node (ref "IC1") (pin "48") (pinfunction "VDD_3_48") (pintype "passive"))
      (node (ref "IC1") (pin "9") (pinfunction "VDDA/VREF+_9") (pintype "passive"))
      (node (ref "JTAG1") (pin "1") (pinfunction "1_1") (pintype "passive"))
      (node (ref "L1") (pin "1") (pinfunction "1_1") (pintype "passive"))
      (node (ref "R1") (pin "2") (pinfunction "2_2") (pintype "passive"))
      (node (ref "R19") (pin "2") (pinfunction "2_2") (pintype "passive"))
      (node (ref "R2") (pin "2") (pinfunction "2_2") (pintype "passive"))
      (node (ref "R21") (pin "2") (pinfunction "2_2") (pintype "passive"))
      (node (ref "R25") (pin "2") (pinfunction "2_2") (pintype "passive"))
      (node (ref "R28") (pin "2") (pinfunction "2_2") (pintype "passive"))
      (node (ref "R5") (pin "1") (pinfunction "1_1") (pintype "passive"))
      (node (ref "U1") (pin "13") (pinfunction "VCC_13") (pintype "passive"))
      (node (ref "UART1") (pin "1") (pinfunction "1_1") (pintype "passive"))
    )
    (net (code "64") (name "unconnected-(IC1-PA0-Pad10)") (class "Default")
      (node (ref "IC1") (pin "10") (pinfunction "PA0_10") (pintype "passive"))
    )
    (net (code "65") (name "unconnected-(IC1-PA6-Pad16)") (class "Default")
      (node (ref "IC1") (pin "16") (pinfunction "PA6_16") (pintype "passive"))
    )
    (net (code "66") (name "unconnected-(IC1-PA8-Pad29)") (class "Default")
      (node (ref "IC1") (pin "29") (pinfunction "PA8_29") (pintype "passive"))
    )
    (net (code "67") (name "unconnected-(IC1-PA15-Pad38)") (class "Default")
      (node (ref "IC1") (pin "38") (pinfunction "PA15_38") (pintype "passive"))
    )
    (net (code "68") (name "unconnected-(IC1-PB2-Pad20)") (class "Default")
      (node (ref "IC1") (pin "20") (pinfunction "PB2_20") (pintype "passive"))
    )
    (net (code "69") (name "unconnected-(IC1-PB3-Pad39)") (class "Default")
      (node (ref "IC1") (pin "39") (pinfunction "PB3_39") (pintype "passive"))
    )
    (net (code "70") (name "unconnected-(IC1-PB4-Pad40)") (class "Default")
      (node (ref "IC1") (pin "40") (pinfunction "PB4_40") (pintype "passive"))
    )
    (net (code "71") (name "unconnected-(IC1-PB8-Pad45)") (class "Default")
      (node (ref "IC1") (pin "45") (pinfunction "PB8_45") (pintype "passive"))
    )
    (net (code "72") (name "unconnected-(IC1-PB9-Pad46)") (class "Default")
      (node (ref "IC1") (pin "46") (pinfunction "PB9_46") (pintype "passive"))
    )
    (net (code "73") (name "unconnected-(IC1-PB12-Pad25)") (class "Default")
      (node (ref "IC1") (pin "25") (pinfunction "PB12_25") (pintype "passive"))
    )
    (net (code "74") (name "unconnected-(IC1-PB13-Pad26)") (class "Default")
      (node (ref "IC1") (pin "26") (pinfunction "PB13_26") (pintype "passive"))
    )
    (net (code "75") (name "unconnected-(IC1-PB14-Pad27)") (class "Default")
      (node (ref "IC1") (pin "27") (pinfunction "PB14_27") (pintype "passive"))
    )
    (net (code "76") (name "unconnected-(IC1-PB15-Pad28)") (class "Default")
      (node (ref "IC1") (pin "28") (pinfunction "PB15_28") (pintype "passive"))
    )
    (net (code "77") (name "unconnected-(IC1-PC14-OSC32_IN-Pad3)") (class "Default")
      (node (ref "IC1") (pin "3") (pinfunction "PC14-OSC32_IN_3") (pintype "passive"))
    )
    (net (code "78") (name "unconnected-(IC1-PC15-OSC32_OUT-Pad4)") (class "Default")
      (node (ref "IC1") (pin "4") (pinfunction "PC15-OSC32_OUT_4") (pintype "passive"))
    )
    (net (code "79") (name "unconnected-(IC1-PH0-OSC_IN-Pad5)") (class "Default")
      (node (ref "IC1") (pin "5") (pinfunction "PH0-OSC_IN_5") (pintype "passive"))
    )
    (net (code "80") (name "unconnected-(IC1-PH1-OSC_OUT-Pad6)") (class "Default")
      (node (ref "IC1") (pin "6") (pinfunction "PH1-OSC_OUT_6") (pintype "passive"))
    )
    (net (code "81") (name "unconnected-(U1-ANT-Pad3)") (class "Default")
      (node (ref "U1") (pin "3") (pinfunction "ANT_3") (pintype "passive"))
    )
    (net (code "82") (name "unconnected-(U1-GND-Pad28)") (class "Default")
      (node (ref "U1") (pin "28") (pinfunction "GND_28") (pintype "passive"))
    )
    (net (code "83") (name "unconnected-(U1-NC-Pad5)") (class "Default")
      (node (ref "U1") (pin "5") (pinfunction "NC_5") (pintype "passive"))
    )
    (net (code "84") (name "unconnected-(U1-NC-Pad6)") (class "Default")
      (node (ref "U1") (pin "6") (pinfunction "NC_6") (pintype "passive"))
    )
    (net (code "85") (name "unconnected-(U1-NC-Pad7)") (class "Default")
      (node (ref "U1") (pin "7") (pinfunction "NC_7") (pintype "passive"))
    )
    (net (code "86") (name "unconnected-(U1-NC-Pad16)") (class "Default")
      (node (ref "U1") (pin "16") (pinfunction "NC_16") (pintype "passive"))
    )
    (net (code "87") (name "unconnected-(U1-NC-Pad19)") (class "Default")
      (node (ref "U1") (pin "19") (pinfunction "NC_19") (pintype "passive"))
    )
    (net (code "88") (name "unconnected-(U1-NC-Pad20)") (class "Default")
      (node (ref "U1") (pin "20") (pinfunction "NC_20") (pintype "passive"))
    )
    (net (code "89") (name "unconnected-(U1-NC-Pad21)") (class "Default")
      (node (ref "U1") (pin "21") (pinfunction "NC_21") (pintype "passive"))
    )
    (net (code "90") (name "unconnected-(U1-NC-Pad22)") (class "Default")
      (node (ref "U1") (pin "22") (pinfunction "NC_22") (pintype "passive"))
    )
    (net (code "91") (name "unconnected-(U1-NC-Pad23)") (class "Default")
      (node (ref "U1") (pin "23") (pinfunction "NC_23") (pintype "passive"))
    )
    (net (code "92") (name "unconnected-(U1-RELOAD-Pad32)") (class "Default")
      (node (ref "U1") (pin "32") (pinfunction "RELOAD_32") (pintype "passive"))
    )
    (net (code "93") (name "unconnected-(U1-RXD-Pad30)") (class "Default")
      (node (ref "U1") (pin "30") (pinfunction "RXD_30") (pintype "passive"))
    )
    (net (code "94") (name "unconnected-(U1-STA-Pad31)") (class "Default")
      (node (ref "U1") (pin "31") (pinfunction "STA_31") (pintype "passive"))
    )
    (net (code "95") (name "unconnected-(U1-TXD-Pad29)") (class "Default")
      (node (ref "U1") (pin "29") (pinfunction "TXD_29") (pintype "passive"))
    )
    (net (code "96") (name "unconnected-(U1-VCC-Pad27)") (class "Default")
      (node (ref "U1") (pin "27") (pinfunction "VCC_27") (pintype "passive"))
    )
  )
)
